# ProDoc_USB2_0__2024-09-16.net
KiCad netlist of a schematic drawn in EasyEDA Pro
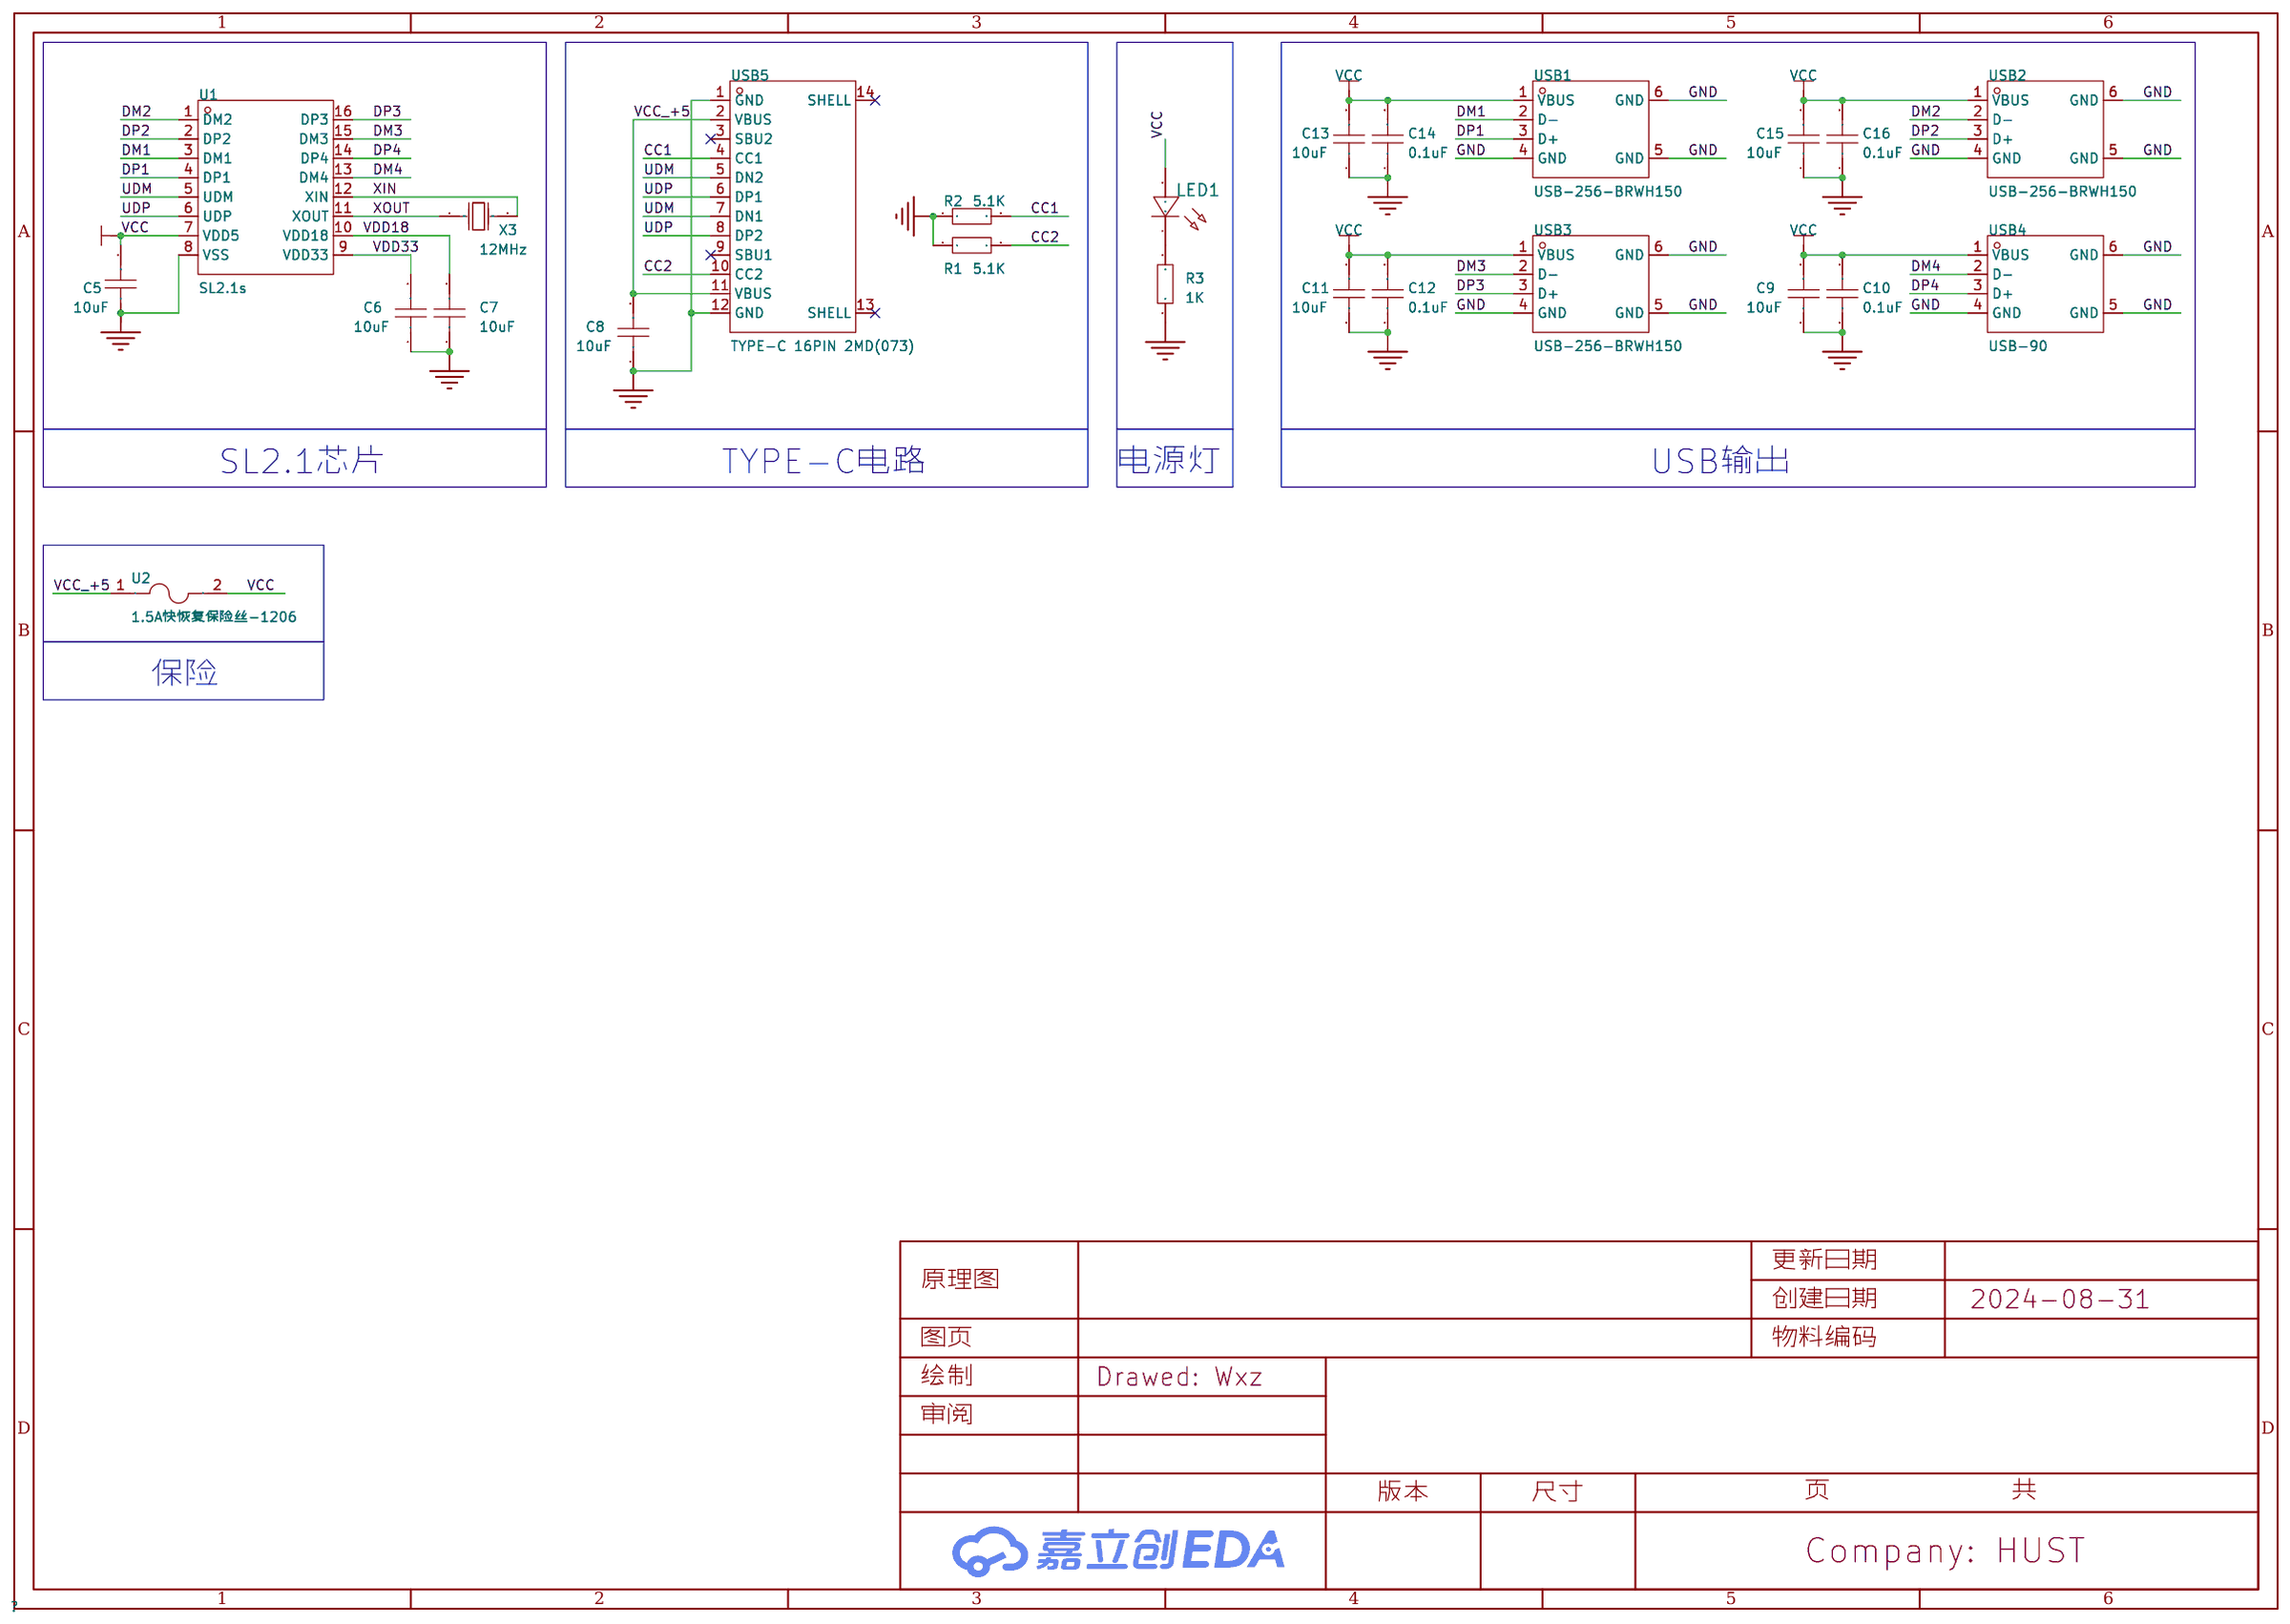
[diagram p0: schematic sheet]

(export (version "E")
  (design (tool "Eeschema 10.0.6"))
  (components
    (comp (ref "C5")
      (value "10uF")
      (footprint "easyedapro:C0603")
      (libsource (lib "easyedapro") (part "CapAcitance"))
    )
    (comp (ref "C6")
      (value "10uF")
      (footprint "easyedapro:C0603")
      (libsource (lib "easyedapro") (part "CapAcitance"))
    )
    (comp (ref "C7")
      (value "10uF")
      (footprint "easyedapro:C0603")
      (libsource (lib "easyedapro") (part "CapAcitance"))
    )
    (comp (ref "C8")
      (value "10uF")
      (footprint "easyedapro:C0603")
      (libsource (lib "easyedapro") (part "CapAcitance"))
    )
    (comp (ref "C9")
      (value "10uF")
      (footprint "easyedapro:C0603")
      (libsource (lib "easyedapro") (part "CapAcitance"))
    )
    (comp (ref "C10")
      (value "0.1uF")
      (footprint "easyedapro:C0603")
      (libsource (lib "easyedapro") (part "CapAcitance"))
    )
    (comp (ref "C11")
      (value "10uF")
      (footprint "easyedapro:C0603")
      (libsource (lib "easyedapro") (part "CapAcitance"))
    )
    (comp (ref "C12")
      (value "0.1uF")
      (footprint "easyedapro:C0603")
      (libsource (lib "easyedapro") (part "CapAcitance"))
    )
    (comp (ref "C13")
      (value "10uF")
      (footprint "easyedapro:C0603")
      (libsource (lib "easyedapro") (part "CapAcitance"))
    )
    (comp (ref "C14")
      (value "0.1uF")
      (footprint "easyedapro:C0603")
      (libsource (lib "easyedapro") (part "CapAcitance"))
    )
    (comp (ref "C15")
      (value "10uF")
      (footprint "easyedapro:C0603")
      (libsource (lib "easyedapro") (part "CapAcitance"))
    )
    (comp (ref "C16")
      (value "0.1uF")
      (footprint "easyedapro:C0603")
      (libsource (lib "easyedapro") (part "CapAcitance"))
    )
    (comp (ref "LED1")
      (value "~")
      (footprint "easyedapro:LED_0603")
      (libsource (lib "easyedapro") (part "LED_R"))
    )
    (comp (ref "R1") (value "5.1K") (footprint "easyedapro:R0603") (libsource (lib "easyedapro") (part "电阻")))
    (comp (ref "R2") (value "5.1K") (footprint "easyedapro:R0603") (libsource (lib "easyedapro") (part "电阻")))
    (comp (ref "R3") (value "1K") (footprint "easyedapro:R0603") (libsource (lib "easyedapro") (part "电阻")))
    (comp (ref "U1")
      (value "SL2.1s")
      (footprint "easyedapro:SSOP-16_L4.6-W2.6-P0.53-LS4.0-BL")
      (description "应用功能:集线器;接口协议:-;")
      (fields (field (name "Manufacturer") "CoreChips(和芯润德)"))
      (libsource (lib "easyedapro") (part "SL2.1S"))
    )
    (comp (ref "U2")
      (value "1.5A快恢复保险丝-1206")
      (footprint "easyedapro:F1206")
      (libsource (lib "easyedapro") (part "1.5A快恢复保险丝-1206"))
    )
    (comp (ref "USB1")
      (value "USB-256-BRWH150")
      (footprint "easyedapro:USB-A_TH_USB-256-BRWH150")
      (fields (field (name "Manufacturer") "XUNPU(讯普)"))
      (libsource (lib "easyedapro") (part "USB-256-BRWH150"))
    )
    (comp (ref "USB2")
      (value "USB-256-BRWH150")
      (footprint "easyedapro:USB-A_TH_USB-256-BRWH150")
      (fields (field (name "Manufacturer") "XUNPU(讯普)"))
      (libsource (lib "easyedapro") (part "USB-256-BRWH150"))
    )
    (comp (ref "USB3")
      (value "USB-256-BRWH150")
      (footprint "easyedapro:USB-A_TH_USB-256-BRWH150")
      (fields (field (name "Manufacturer") "XUNPU(讯普)"))
      (libsource (lib "easyedapro") (part "USB-256-BRWH150"))
    )
    (comp (ref "USB4")
      (value "USB-90")
      (footprint "easyedapro:USB-A-TH_USB-231-ARY")
      (fields (field (name "Manufacturer") "XUNPU(讯普)"))
      (libsource (lib "easyedapro") (part "USB-231-BRW"))
    )
    (comp (ref "USB5")
      (value "TYPE-C 16PIN 2MD(073)")
      (footprint "easyedapro:USB-C-SMD_TYPE-C-6PIN-2MD-073")
      (description "连接器类型:Type-C;标准:-;公母:母;端口数量:1;触点数量:16P;安装方式:卧贴;额定电流 - 电源:5A;工作温度范围:-25°C~+85°C;")
      (fields (field (name "Manufacturer") "SHOU HAN(首韩)"))
      (libsource (lib "easyedapro") (part "TYPE-C 16PIN 2MD(073)"))
    )
    (comp (ref "X3")
      (value "12MHz")
      (footprint "easyedapro:HC-49S_L11.4-W4.8")
      (description "晶振类型:贴片晶振;频率:12MHz;常温频差:±20ppm;外接负载电容:20pF;频率稳定度(全温):±30ppm;")
      (fields (field (name "Manufacturer Part") "X49SM12MSD2SI") (field (name "Manufacturer") "YXC(扬兴晶振)"))
      (libsource (lib "easyedapro") (part "X49SM12MSD2SI"))
    )
  )
  (nets
    (net (code "1") (name "/CC1") (class "Default")
      (node (ref "R2") (pin "2") (pinfunction "2_2") (pintype "input"))
      (node (ref "USB5") (pin "4") (pinfunction "CC1_4") (pintype "unspecified"))
    )
    (net (code "2") (name "/CC2") (class "Default")
      (node (ref "R1") (pin "2") (pinfunction "2_2") (pintype "input"))
      (node (ref "USB5") (pin "10") (pinfunction "CC2_10") (pintype "unspecified"))
    )
    (net (code "3") (name "/DM1") (class "Default")
      (node (ref "U1") (pin "3") (pinfunction "DM1_3") (pintype "unspecified"))
      (node (ref "USB1") (pin "2") (pinfunction "D-_2") (pintype "unspecified"))
    )
    (net (code "4") (name "/DM2") (class "Default")
      (node (ref "U1") (pin "1") (pinfunction "DM2_1") (pintype "unspecified"))
      (node (ref "USB2") (pin "2") (pinfunction "D-_2") (pintype "unspecified"))
    )
    (net (code "5") (name "/DM3") (class "Default")
      (node (ref "U1") (pin "15") (pinfunction "DM3_15") (pintype "unspecified"))
      (node (ref "USB3") (pin "2") (pinfunction "D-_2") (pintype "unspecified"))
    )
    (net (code "6") (name "/DM4") (class "Default")
      (node (ref "U1") (pin "13") (pinfunction "DM4_13") (pintype "unspecified"))
      (node (ref "USB4") (pin "2") (pinfunction "D-_2") (pintype "unspecified"))
    )
    (net (code "7") (name "/DP1") (class "Default")
      (node (ref "U1") (pin "4") (pinfunction "DP1_4") (pintype "unspecified"))
      (node (ref "USB1") (pin "3") (pinfunction "D+_3") (pintype "unspecified"))
    )
    (net (code "8") (name "/DP2") (class "Default")
      (node (ref "U1") (pin "2") (pinfunction "DP2_2") (pintype "unspecified"))
      (node (ref "USB2") (pin "3") (pinfunction "D+_3") (pintype "unspecified"))
    )
    (net (code "9") (name "/DP3") (class "Default")
      (node (ref "U1") (pin "16") (pinfunction "DP3_16") (pintype "unspecified"))
      (node (ref "USB3") (pin "3") (pinfunction "D+_3") (pintype "unspecified"))
    )
    (net (code "10") (name "/DP4") (class "Default")
      (node (ref "U1") (pin "14") (pinfunction "DP4_14") (pintype "unspecified"))
      (node (ref "USB4") (pin "3") (pinfunction "D+_3") (pintype "unspecified"))
    )
    (net (code "11") (name "/UDM") (class "Default")
      (node (ref "U1") (pin "5") (pinfunction "UDM_5") (pintype "unspecified"))
      (node (ref "USB5") (pin "5") (pinfunction "DN2_5") (pintype "unspecified"))
      (node (ref "USB5") (pin "7") (pinfunction "DN1_7") (pintype "unspecified"))
    )
    (net (code "12") (name "/UDP") (class "Default")
      (node (ref "U1") (pin "6") (pinfunction "UDP_6") (pintype "unspecified"))
      (node (ref "USB5") (pin "6") (pinfunction "DP1_6") (pintype "unspecified"))
      (node (ref "USB5") (pin "8") (pinfunction "DP2_8") (pintype "unspecified"))
    )
    (net (code "13") (name "/VCC_+5") (class "Default")
      (node (ref "C8") (pin "2") (pinfunction "2_2") (pintype "input"))
      (node (ref "U2") (pin "1") (pinfunction "1_1") (pintype "unspecified"))
      (node (ref "USB5") (pin "11") (pinfunction "VBUS_11") (pintype "unspecified"))
      (node (ref "USB5") (pin "2") (pinfunction "VBUS_2") (pintype "unspecified"))
    )
    (net (code "14") (name "/VDD18") (class "Default")
      (node (ref "C7") (pin "2") (pinfunction "2_2") (pintype "input"))
      (node (ref "U1") (pin "10") (pinfunction "VDD18_10") (pintype "unspecified"))
    )
    (net (code "15") (name "/VDD33") (class "Default")
      (node (ref "C6") (pin "2") (pinfunction "2_2") (pintype "input"))
      (node (ref "U1") (pin "9") (pinfunction "VDD33_9") (pintype "unspecified"))
    )
    (net (code "16") (name "/XIN") (class "Default")
      (node (ref "U1") (pin "12") (pinfunction "XIN_12") (pintype "unspecified"))
      (node (ref "X3") (pin "2") (pinfunction "OSC2_2") (pintype "input"))
    )
    (net (code "17") (name "/XOUT") (class "Default")
      (node (ref "U1") (pin "11") (pinfunction "XOUT_11") (pintype "unspecified"))
      (node (ref "X3") (pin "1") (pinfunction "OSC1_1") (pintype "input"))
    )
    (net (code "18") (name "GND") (class "Default")
      (node (ref "C10") (pin "1") (pinfunction "1_1") (pintype "input"))
      (node (ref "C11") (pin "1") (pinfunction "1_1") (pintype "input"))
      (node (ref "C12") (pin "1") (pinfunction "1_1") (pintype "input"))
      (node (ref "C13") (pin "1") (pinfunction "1_1") (pintype "input"))
      (node (ref "C14") (pin "1") (pinfunction "1_1") (pintype "input"))
      (node (ref "C15") (pin "1") (pinfunction "1_1") (pintype "input"))
      (node (ref "C16") (pin "1") (pinfunction "1_1") (pintype "input"))
      (node (ref "C5") (pin "1") (pinfunction "1_1") (pintype "input"))
      (node (ref "C6") (pin "1") (pinfunction "1_1") (pintype "input"))
      (node (ref "C7") (pin "1") (pinfunction "1_1") (pintype "input"))
      (node (ref "C8") (pin "1") (pinfunction "1_1") (pintype "input"))
      (node (ref "C9") (pin "1") (pinfunction "1_1") (pintype "input"))
      (node (ref "R1") (pin "1") (pinfunction "1_1") (pintype "input"))
      (node (ref "R2") (pin "1") (pinfunction "1_1") (pintype "input"))
      (node (ref "R3") (pin "1") (pinfunction "1_1") (pintype "input"))
      (node (ref "U1") (pin "8") (pinfunction "VSS_8") (pintype "unspecified"))
      (node (ref "USB1") (pin "4") (pinfunction "GND_4") (pintype "unspecified"))
      (node (ref "USB1") (pin "5") (pinfunction "GND_5") (pintype "unspecified"))
      (node (ref "USB1") (pin "6") (pinfunction "GND_6") (pintype "unspecified"))
      (node (ref "USB2") (pin "4") (pinfunction "GND_4") (pintype "unspecified"))
      (node (ref "USB2") (pin "5") (pinfunction "GND_5") (pintype "unspecified"))
      (node (ref "USB2") (pin "6") (pinfunction "GND_6") (pintype "unspecified"))
      (node (ref "USB3") (pin "4") (pinfunction "GND_4") (pintype "unspecified"))
      (node (ref "USB3") (pin "5") (pinfunction "GND_5") (pintype "unspecified"))
      (node (ref "USB3") (pin "6") (pinfunction "GND_6") (pintype "unspecified"))
      (node (ref "USB4") (pin "4") (pinfunction "GND_4") (pintype "unspecified"))
      (node (ref "USB4") (pin "5") (pinfunction "GND_5") (pintype "unspecified"))
      (node (ref "USB4") (pin "6") (pinfunction "GND_6") (pintype "unspecified"))
      (node (ref "USB5") (pin "1") (pinfunction "GND_1") (pintype "unspecified"))
      (node (ref "USB5") (pin "12") (pinfunction "GND_12") (pintype "unspecified"))
    )
    (net (code "19") (name "Net-(LED1-C)") (class "Default")
      (node (ref "LED1") (pin "1") (pinfunction "C_1") (pintype "input"))
      (node (ref "R3") (pin "2") (pinfunction "2_2") (pintype "input"))
    )
    (net (code "20") (name "VCC") (class "Default")
      (node (ref "C10") (pin "2") (pinfunction "2_2") (pintype "input"))
      (node (ref "C11") (pin "2") (pinfunction "2_2") (pintype "input"))
      (node (ref "C12") (pin "2") (pinfunction "2_2") (pintype "input"))
      (node (ref "C13") (pin "2") (pinfunction "2_2") (pintype "input"))
      (node (ref "C14") (pin "2") (pinfunction "2_2") (pintype "input"))
      (node (ref "C15") (pin "2") (pinfunction "2_2") (pintype "input"))
      (node (ref "C16") (pin "2") (pinfunction "2_2") (pintype "input"))
      (node (ref "C5") (pin "2") (pinfunction "2_2") (pintype "input"))
      (node (ref "C9") (pin "2") (pinfunction "2_2") (pintype "input"))
      (node (ref "LED1") (pin "2") (pinfunction "A_2") (pintype "input"))
      (node (ref "U1") (pin "7") (pinfunction "VDD5_7") (pintype "unspecified"))
      (node (ref "U2") (pin "2") (pinfunction "2_2") (pintype "unspecified"))
      (node (ref "USB1") (pin "1") (pinfunction "VBUS_1") (pintype "unspecified"))
      (node (ref "USB2") (pin "1") (pinfunction "VBUS_1") (pintype "unspecified"))
      (node (ref "USB3") (pin "1") (pinfunction "VBUS_1") (pintype "unspecified"))
      (node (ref "USB4") (pin "1") (pinfunction "VBUS_1") (pintype "unspecified"))
    )
    (net (code "21") (name "unconnected-(USB5-SBU1-Pad9)") (class "Default")
      (node (ref "USB5") (pin "9") (pinfunction "SBU1_9") (pintype "unspecified+no_connect"))
    )
    (net (code "22") (name "unconnected-(USB5-SBU2-Pad3)") (class "Default")
      (node (ref "USB5") (pin "3") (pinfunction "SBU2_3") (pintype "unspecified+no_connect"))
    )
    (net (code "23") (name "unconnected-(USB5-SHELL-Pad13)") (class "Default")
      (node (ref "USB5") (pin "13") (pinfunction "SHELL_13") (pintype "unspecified+no_connect"))
    )
    (net (code "24") (name "unconnected-(USB5-SHELL-Pad14)") (class "Default")
      (node (ref "USB5") (pin "14") (pinfunction "SHELL_14") (pintype "unspecified+no_connect"))
    )
  )
)
